# WemosESP8266.net
KiCad netlist of a schematic drawn in Altium Designer
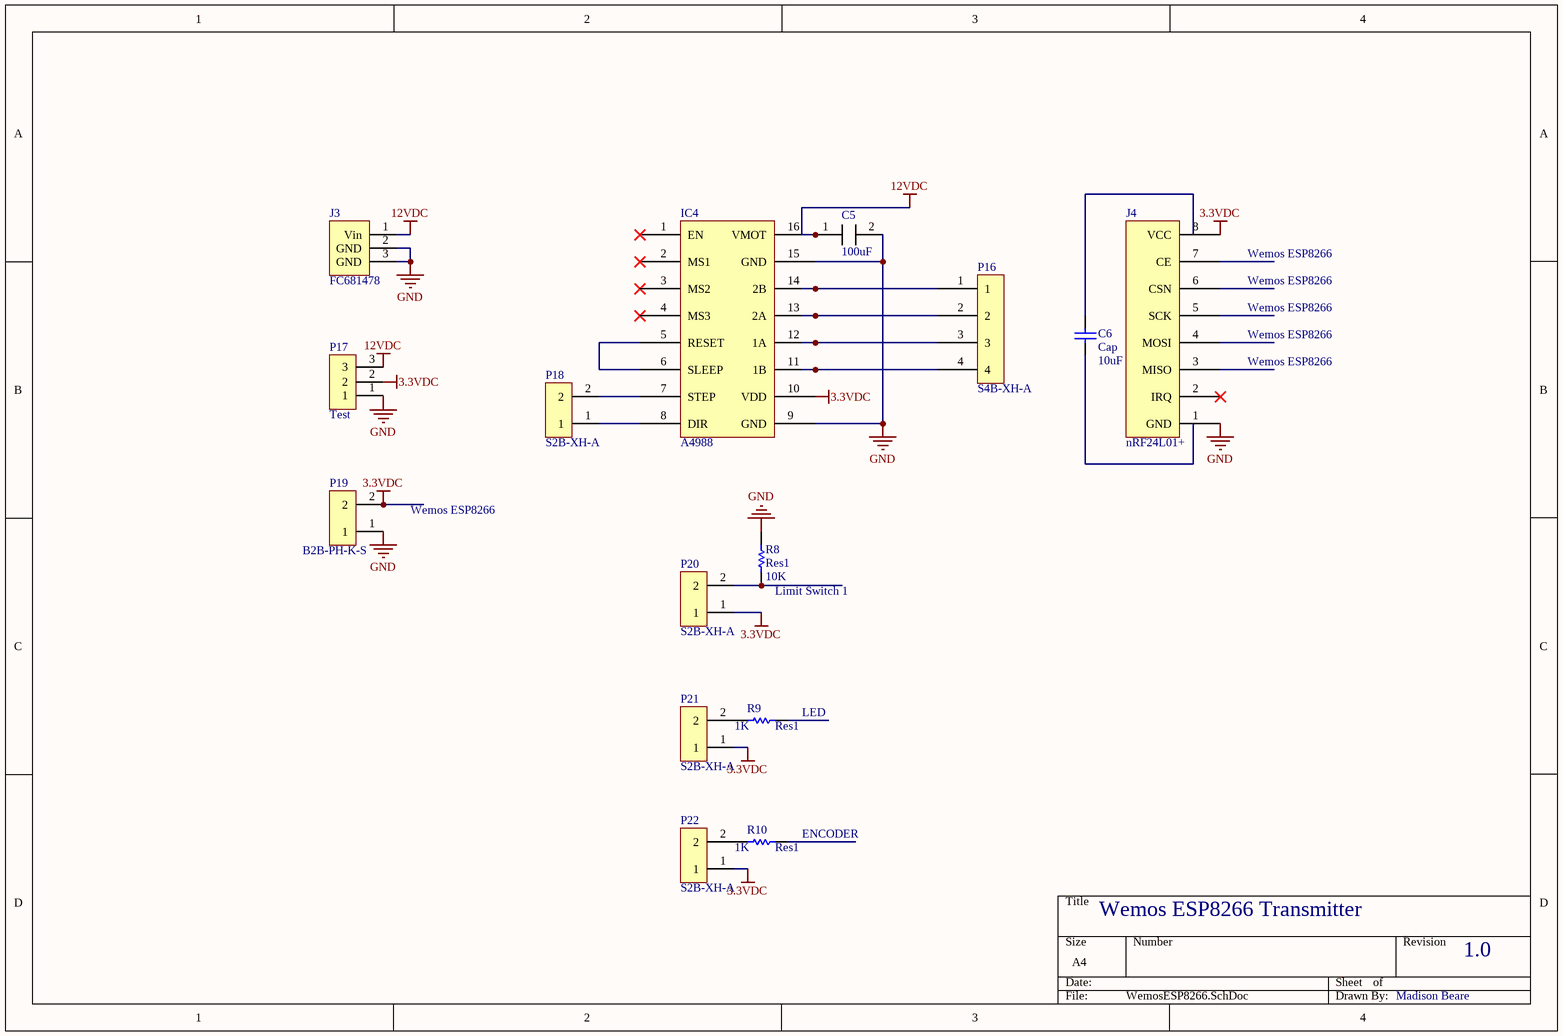
[diagram p0: WemosESP8266.SchDoc]

(export (version "E")
  (design (tool "Eeschema 10.0.6"))
  (components
    (comp (ref "C5")
      (value "100uF")
      (footprint "EEE-FP1H101AP")
      (description "100uF capacitor smd 8.3x8.3 dimensions")
      (libsource (lib "EEE-FP1H101AP") (part "EEE-FP1H101AP"))
    )
    (comp (ref "C6")
      (value "Cap")
      (footprint "RAD-0.3")
      (description "Capacitor")
      (fields (field (name "ALTIUM_VALUE") "10uF") (field (name "PUBLISHER") "Altium Limited"))
      (libsource (lib "Miscellaneous Devices") (part "Cap"))
    )
    (comp (ref "IC4") (value "A4988") (libsource (lib "theMonarchTransmitter_SchLib") (part "a4988")))
    (comp (ref "J3")
      (value "FC681478")
      (description "CLIFF ELECTRONIC COMPONENTS         FC681478            CONNECTOR, POWER ENTRY, RCPT, 2A, 16VDC")
      (fields (field (name "MANUFACTURER") "Cliff"))
      (libsource (lib "theMonarchTransmitter_SchLib") (part "FC681478"))
    )
    (comp (ref "J4")
      (value "nRF24L01+")
      (description "SPARKFUN TRANSCEIVER BREAKOUT -")
      (fields (field (name "MANUFACTURER") "SparkFun") (field (name "MANUFACTURER PART NUMBER") "WRL-00691"))
      (libsource (lib "theMonarchTransmitter_SchLib") (part "WRL-00691"))
    )
    (comp (ref "P16")
      (value "S4B-XH-A")
      (description "Conn Shrouded Header HDR 4 POS 2.5mm Solder RA Thru-Hole Box")
      (fields
        (field (name "MANUFACTURER") "JST")
        (field (name "MANUFACTURER PART NUMBER") "S4B-XH-A(LF)(SN)")
      )
      (libsource (lib "theMonarchTransmitter_SchLib") (part "S4B-XH-A(LF)(SN)"))
    )
    (comp (ref "P17") (value "Test") (libsource (lib "theMonarchTransmitter_SchLib") (part "Test_Header")))
    (comp (ref "P18")
      (value "S2B-XH-A")
      (description "Conn Shrouded Header HDR 2 POS 2.5mm Solder RA Thru-Hole Box")
      (fields
        (field (name "MANUFACTURER") "JST")
        (field (name "MANUFACTURER PART NUMBER") "S2B-XH-A(LF)(SN)")
      )
      (libsource (lib "theMonarchTransmitter_SchLib") (part "S2B-XH-A(LF)(SN)"))
    )
    (comp (ref "P19")
      (value "B2B-PH-K-S")
      (description "Connector Header, PH Series, 2 Position, 2.00mm, Through Hole, Press-Fit, Solder, Natural")
      (fields
        (field (name "MANUFACTURER") "JST")
        (field (name "MANUFACTURER PART NUMBER") "B2B-PH-K-S(LF)(SN)")
      )
      (libsource (lib "theMonarchTransmitter_SchLib") (part "B2B-PH-K-S(LF)(SN)"))
    )
    (comp (ref "P20")
      (value "S2B-XH-A")
      (description "Conn Shrouded Header HDR 2 POS 2.5mm Solder RA Thru-Hole Box")
      (fields
        (field (name "MANUFACTURER") "JST")
        (field (name "MANUFACTURER PART NUMBER") "S2B-XH-A(LF)(SN)")
      )
      (libsource (lib "theMonarchTransmitter_SchLib") (part "S2B-XH-A(LF)(SN)"))
    )
    (comp (ref "P21")
      (value "S2B-XH-A")
      (description "Conn Shrouded Header HDR 2 POS 2.5mm Solder RA Thru-Hole Box")
      (fields
        (field (name "MANUFACTURER") "JST")
        (field (name "MANUFACTURER PART NUMBER") "S2B-XH-A(LF)(SN)")
      )
      (libsource (lib "theMonarchTransmitter_SchLib") (part "S2B-XH-A(LF)(SN)"))
    )
    (comp (ref "P22")
      (value "S2B-XH-A")
      (description "Conn Shrouded Header HDR 2 POS 2.5mm Solder RA Thru-Hole Box")
      (fields
        (field (name "MANUFACTURER") "JST")
        (field (name "MANUFACTURER PART NUMBER") "S2B-XH-A(LF)(SN)")
      )
      (libsource (lib "theMonarchTransmitter_SchLib") (part "S2B-XH-A(LF)(SN)"))
    )
    (comp (ref "R8")
      (value "Res1")
      (footprint "AXIAL-0.3")
      (description "Resistor")
      (fields (field (name "ALTIUM_VALUE") "10K") (field (name "PUBLISHER") "Altium Limited"))
      (libsource (lib "Miscellaneous Devices") (part "Res1"))
    )
    (comp (ref "R9")
      (value "Res1")
      (footprint "AXIAL-0.3")
      (description "Resistor")
      (fields (field (name "ALTIUM_VALUE") "1K") (field (name "PUBLISHER") "Altium Limited"))
      (libsource (lib "Miscellaneous Devices") (part "Res1"))
    )
    (comp (ref "R10")
      (value "Res1")
      (footprint "AXIAL-0.3")
      (description "Resistor")
      (fields (field (name "ALTIUM_VALUE") "1K") (field (name "PUBLISHER") "Altium Limited"))
      (libsource (lib "Miscellaneous Devices") (part "Res1"))
    )
  )
  (nets
    (net (code "1") (name "3.3VDC") (class "Default")
      (node (ref "IC4") (pin "10") (pinfunction "VDD_10") (pintype "passive"))
      (node (ref "J4") (pin "8") (pinfunction "VCC_8") (pintype "passive"))
      (node (ref "P17") (pin "2") (pinfunction "2_2") (pintype "passive"))
      (node (ref "P19") (pin "2") (pinfunction "2_2") (pintype "passive"))
      (node (ref "P20") (pin "1") (pinfunction "1_1") (pintype "passive"))
      (node (ref "P21") (pin "1") (pinfunction "1_1") (pintype "passive"))
      (node (ref "P22") (pin "1") (pinfunction "1_1") (pintype "passive"))
    )
    (net (code "2") (name "12VDC") (class "Default")
      (node (ref "C5") (pin "1") (pinfunction "+-_1") (pintype "passive"))
      (node (ref "IC4") (pin "16") (pinfunction "VMOT_16") (pintype "passive"))
      (node (ref "J3") (pin "1") (pinfunction "Vin_1") (pintype "passive"))
      (node (ref "P17") (pin "3") (pinfunction "3_3") (pintype "passive"))
    )
    (net (code "3") (name "GND") (class "Default")
      (node (ref "C5") (pin "2") (pintype "passive"))
      (node (ref "IC4") (pin "15") (pinfunction "GND_15") (pintype "passive"))
      (node (ref "IC4") (pin "9") (pinfunction "GND_9") (pintype "passive"))
      (node (ref "J3") (pin "2") (pinfunction "GND_2") (pintype "passive"))
      (node (ref "J3") (pin "3") (pinfunction "GND_3") (pintype "passive"))
      (node (ref "J4") (pin "1") (pinfunction "GND_1") (pintype "passive"))
      (node (ref "P19") (pin "1") (pinfunction "1_1") (pintype "passive"))
      (node (ref "R8") (pin "2") (pinfunction "2_2") (pintype "passive"))
    )
    (net (code "4") (name "Net-(IC4-1A)") (class "Default")
      (node (ref "IC4") (pin "12") (pinfunction "1A_12") (pintype "passive"))
      (node (ref "P16") (pin "3") (pinfunction "3_3") (pintype "passive"))
    )
    (net (code "5") (name "Net-(IC4-1B)") (class "Default")
      (node (ref "IC4") (pin "11") (pinfunction "1B_11") (pintype "passive"))
      (node (ref "P16") (pin "4") (pinfunction "4_4") (pintype "passive"))
    )
    (net (code "6") (name "Net-(IC4-2A)") (class "Default")
      (node (ref "IC4") (pin "13") (pinfunction "2A_13") (pintype "passive"))
      (node (ref "P16") (pin "2") (pinfunction "2_2") (pintype "passive"))
    )
    (net (code "7") (name "Net-(IC4-2B)") (class "Default")
      (node (ref "IC4") (pin "14") (pinfunction "2B_14") (pintype "passive"))
      (node (ref "P16") (pin "1") (pinfunction "1_1") (pintype "passive"))
    )
    (net (code "8") (name "Net-(IC4-DIR)") (class "Default")
      (node (ref "IC4") (pin "8") (pinfunction "DIR_8") (pintype "passive"))
      (node (ref "P18") (pin "1") (pinfunction "1_1") (pintype "passive"))
    )
    (net (code "9") (name "Net-(IC4-RESET)") (class "Default")
      (node (ref "IC4") (pin "5") (pinfunction "RESET_5") (pintype "passive"))
      (node (ref "IC4") (pin "6") (pinfunction "SLEEP_6") (pintype "passive"))
    )
    (net (code "10") (name "Net-(IC4-STEP)") (class "Default")
      (node (ref "IC4") (pin "7") (pinfunction "STEP_7") (pintype "passive"))
      (node (ref "P18") (pin "2") (pinfunction "2_2") (pintype "passive"))
    )
    (net (code "11") (name "Net-(P20-Pad2)") (class "Default")
      (node (ref "P20") (pin "2") (pinfunction "2_2") (pintype "passive"))
      (node (ref "R8") (pin "1") (pinfunction "1_1") (pintype "passive"))
    )
    (net (code "12") (name "Net-(P21-Pad2)") (class "Default")
      (node (ref "P21") (pin "2") (pinfunction "2_2") (pintype "passive"))
      (node (ref "R9") (pin "1") (pinfunction "1_1") (pintype "passive"))
    )
    (net (code "13") (name "Net-(P22-Pad2)") (class "Default")
      (node (ref "P22") (pin "2") (pinfunction "2_2") (pintype "passive"))
      (node (ref "R10") (pin "1") (pinfunction "1_1") (pintype "passive"))
    )
    (net (code "14") (name "unconnected-(C6-Pad1)") (class "Default")
      (node (ref "C6") (pin "1") (pinfunction "1_1") (pintype "passive"))
    )
    (net (code "15") (name "unconnected-(C6-Pad2)") (class "Default")
      (node (ref "C6") (pin "2") (pinfunction "2_2") (pintype "passive"))
    )
    (net (code "16") (name "unconnected-(IC4-EN-Pad1)") (class "Default")
      (node (ref "IC4") (pin "1") (pinfunction "EN_1") (pintype "passive+no_connect"))
    )
    (net (code "17") (name "unconnected-(IC4-MS1-Pad2)") (class "Default")
      (node (ref "IC4") (pin "2") (pinfunction "MS1_2") (pintype "passive+no_connect"))
    )
    (net (code "18") (name "unconnected-(IC4-MS2-Pad3)") (class "Default")
      (node (ref "IC4") (pin "3") (pinfunction "MS2_3") (pintype "passive+no_connect"))
    )
    (net (code "19") (name "unconnected-(IC4-MS3-Pad4)") (class "Default")
      (node (ref "IC4") (pin "4") (pinfunction "MS3_4") (pintype "passive+no_connect"))
    )
    (net (code "20") (name "unconnected-(J4-CE-Pad7)") (class "Default")
      (node (ref "J4") (pin "7") (pinfunction "CE_7") (pintype "passive"))
    )
    (net (code "21") (name "unconnected-(J4-CSN-Pad6)") (class "Default")
      (node (ref "J4") (pin "6") (pinfunction "CSN_6") (pintype "passive"))
    )
    (net (code "22") (name "unconnected-(J4-IRQ-Pad2)") (class "Default")
      (node (ref "J4") (pin "2") (pinfunction "IRQ_2") (pintype "passive+no_connect"))
    )
    (net (code "23") (name "unconnected-(J4-MISO-Pad3)") (class "Default")
      (node (ref "J4") (pin "3") (pinfunction "MISO_3") (pintype "passive"))
    )
    (net (code "24") (name "unconnected-(J4-MOSI-Pad4)") (class "Default")
      (node (ref "J4") (pin "4") (pinfunction "MOSI_4") (pintype "passive"))
    )
    (net (code "25") (name "unconnected-(J4-SCK-Pad5)") (class "Default")
      (node (ref "J4") (pin "5") (pinfunction "SCK_5") (pintype "passive"))
    )
    (net (code "26") (name "unconnected-(P17-Pad1)") (class "Default")
      (node (ref "P17") (pin "1") (pinfunction "1_1") (pintype "passive"))
    )
    (net (code "27") (name "unconnected-(R9-Pad2)") (class "Default")
      (node (ref "R9") (pin "2") (pinfunction "2_2") (pintype "passive"))
    )
    (net (code "28") (name "unconnected-(R10-Pad2)") (class "Default")
      (node (ref "R10") (pin "2") (pinfunction "2_2") (pintype "passive"))
    )
  )
)
